# MODULE.net
KiCad netlist of a schematic drawn in Altium Designer
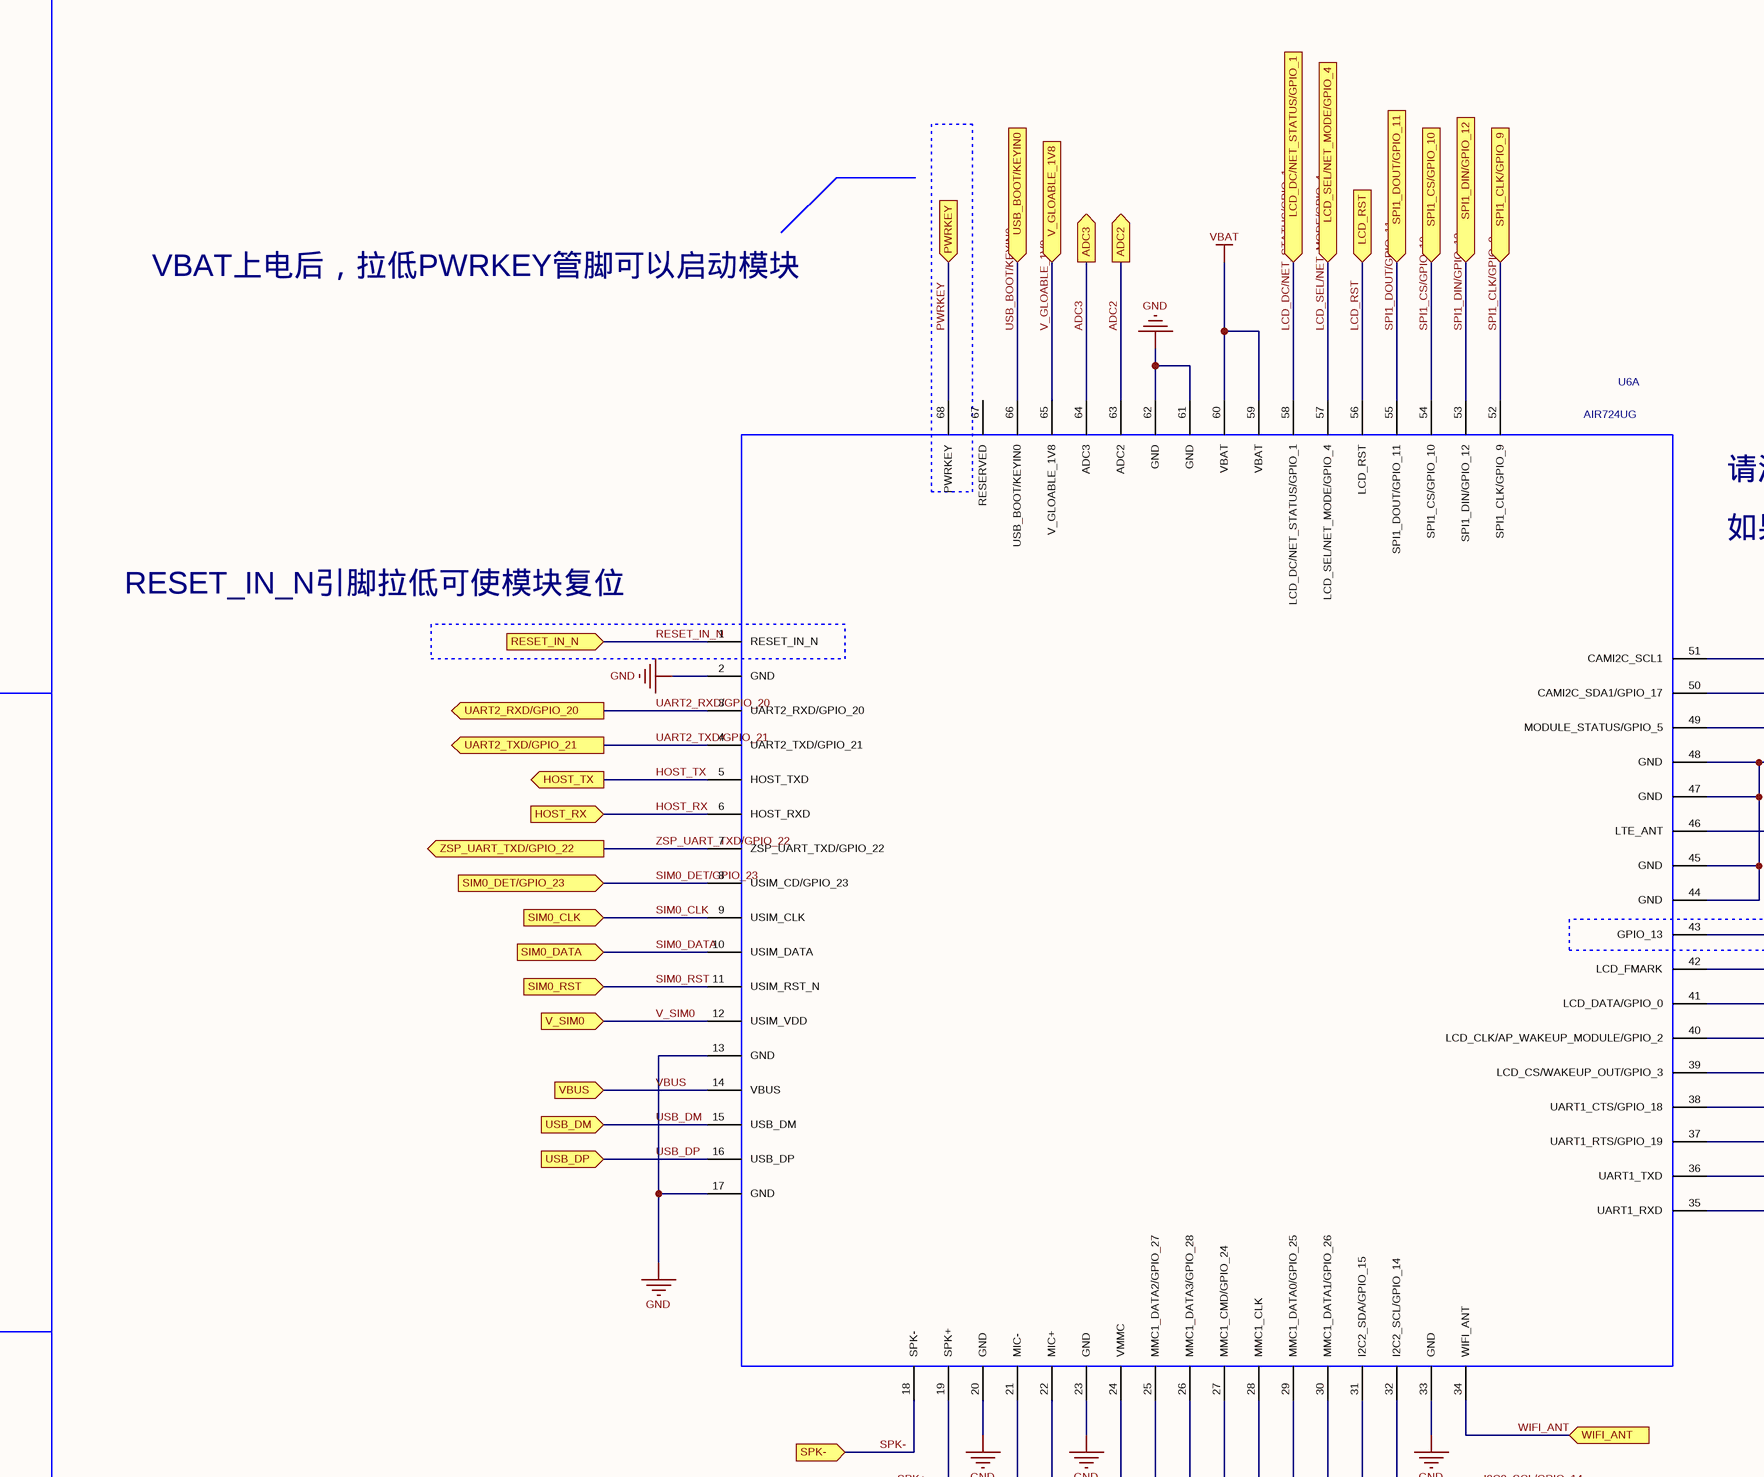
[diagram p0: MODULE.SchDoc, top left]
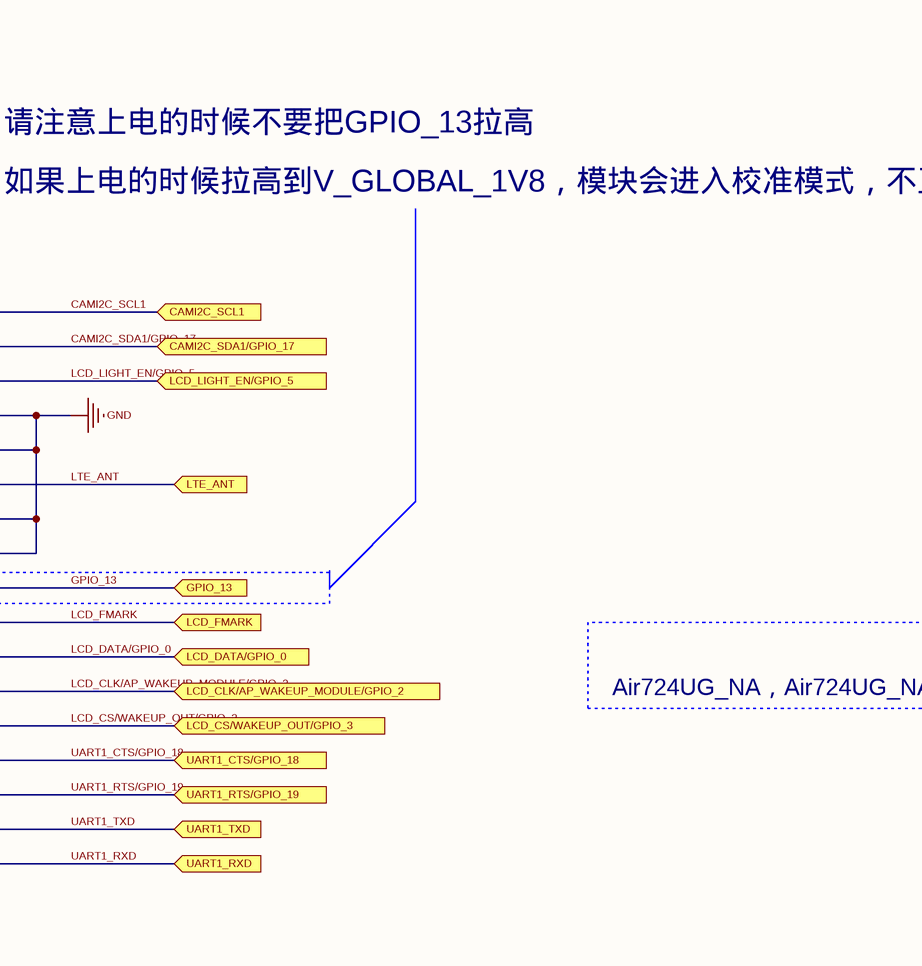
[diagram p1: MODULE.SchDoc, top middle]
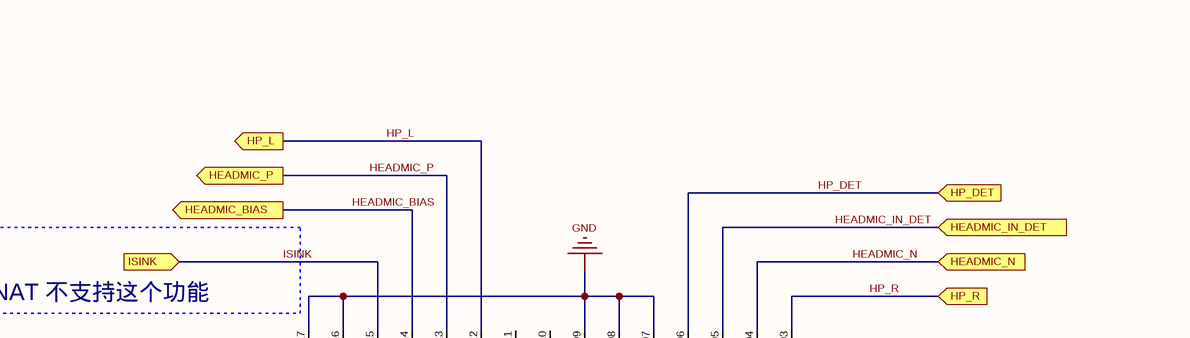
[diagram p2: MODULE.SchDoc, top right]
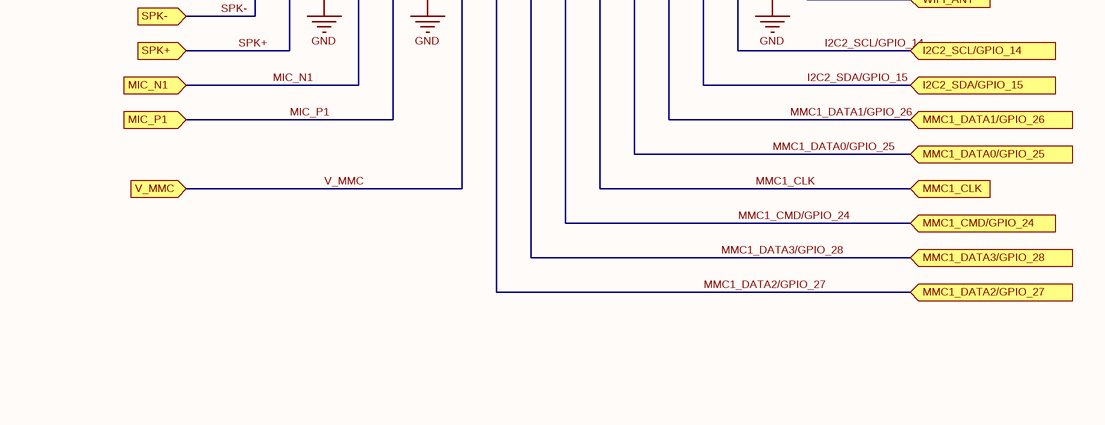
[diagram p3: MODULE.SchDoc, bottom left]
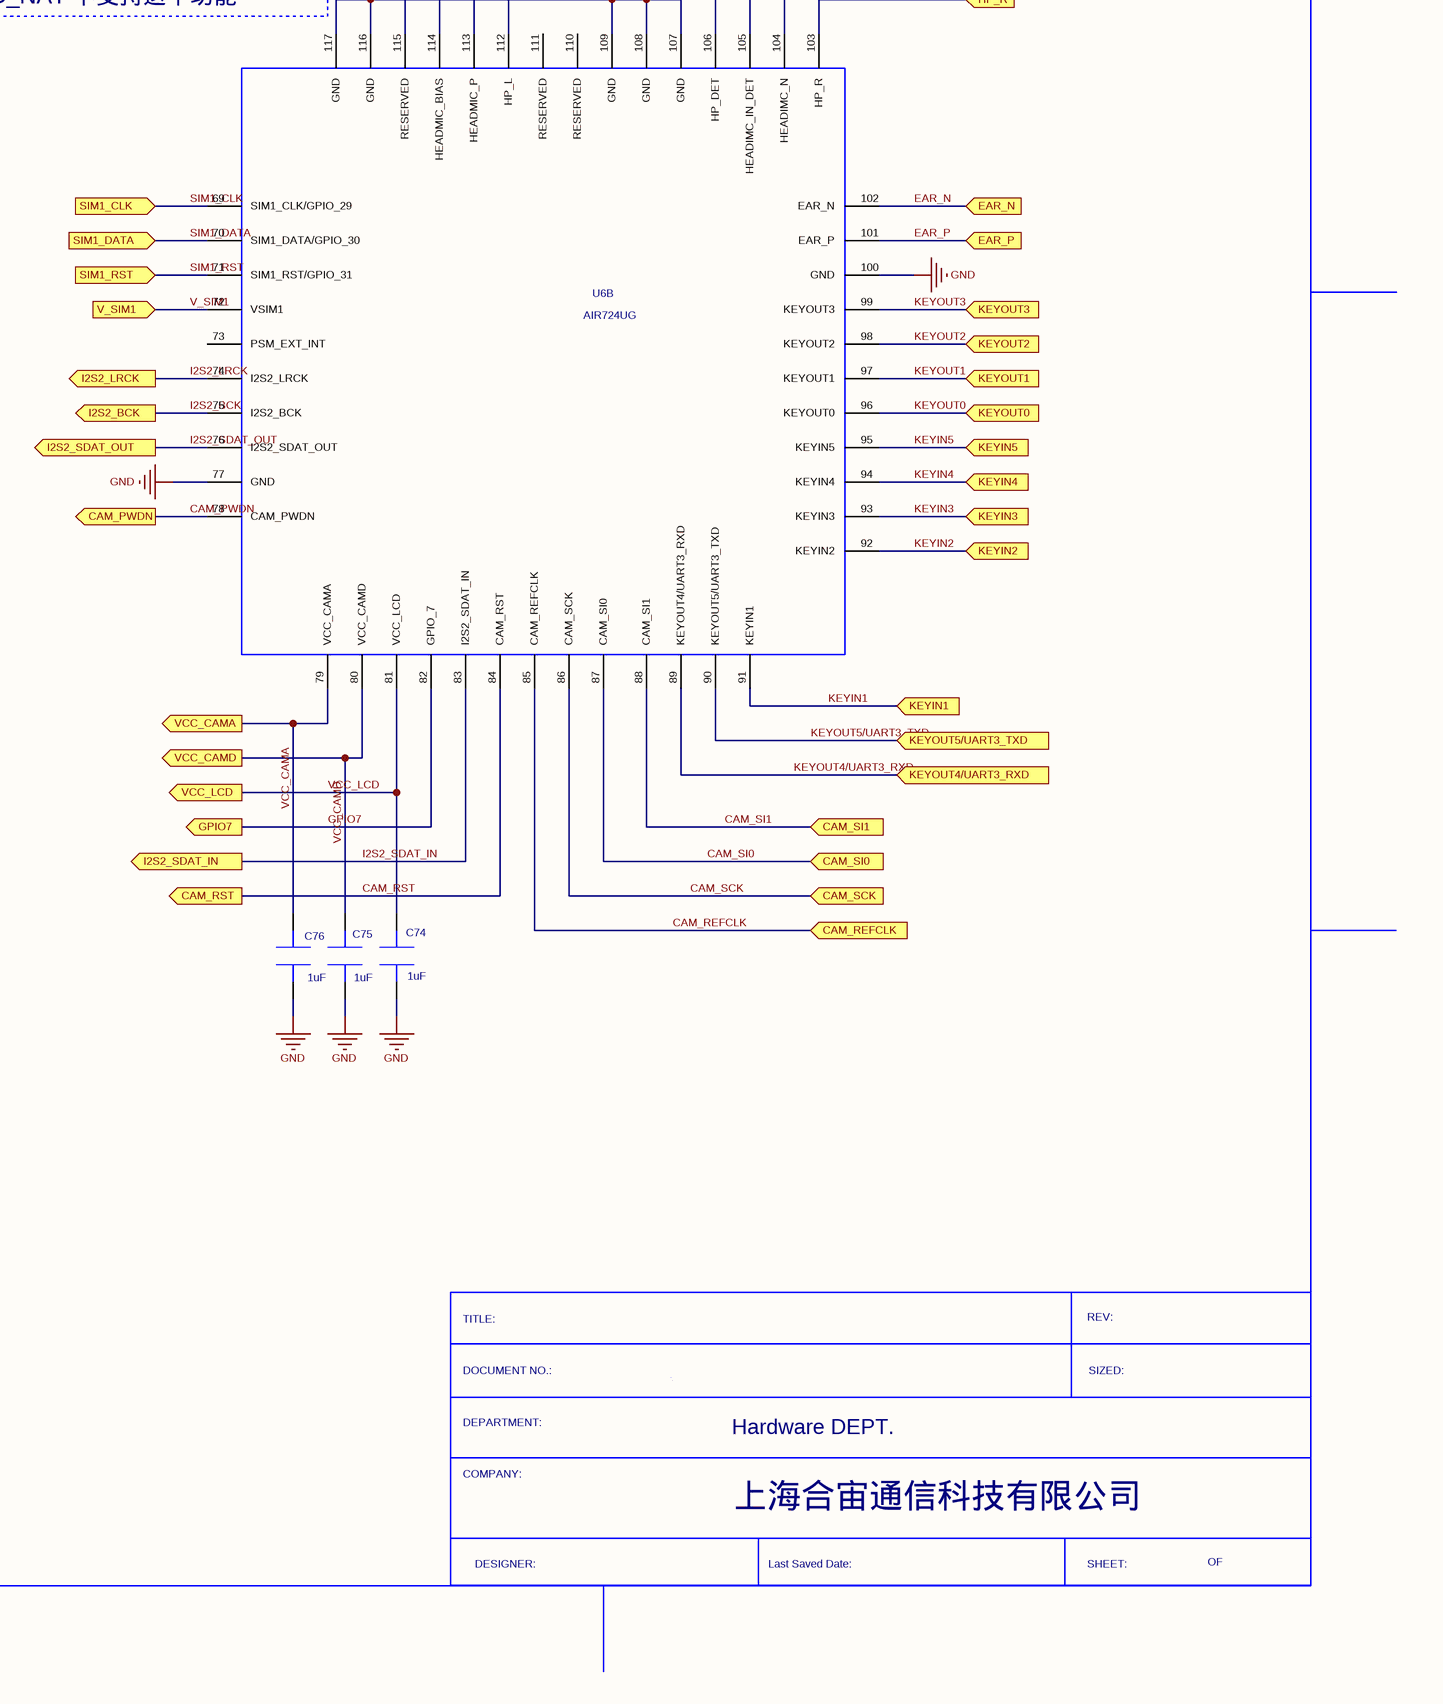
[diagram p4: MODULE.SchDoc, bottom right]

(export (version "E")
  (design (tool "Eeschema 10.0.6"))
  (components
    (comp (ref "C74")
      (value "1uF")
      (footprint "SC0402")
      (description "CAP CER X5R;1uF;+/-10%;6.3V;0402;0.5mm;ROHS")
      (fields (field (name "TOLERANCE") "+/-10%") (field (name "Comment") "CAP-1UF-0402-X5R"))
      (libsource (lib "*") (part "CAP-1UF-0402-X5R"))
    )
    (comp (ref "C75")
      (value "1uF")
      (footprint "SC0402")
      (description "CAP CER X5R;1uF;+/-10%;6.3V;0402;0.5mm;ROHS")
      (fields (field (name "TOLERANCE") "+/-10%") (field (name "Comment") "CAP-1UF-0402-X5R"))
      (libsource (lib "*") (part "CAP-1UF-0402-X5R"))
    )
    (comp (ref "C76")
      (value "1uF")
      (footprint "SC0402")
      (description "CAP CER X5R;1uF;+/-10%;6.3V;0402;0.5mm;ROHS")
      (fields (field (name "TOLERANCE") "+/-10%") (field (name "Comment") "CAP-1UF-0402-X5R"))
      (libsource (lib "*") (part "CAP-1UF-0402-X5R"))
    )
    (comp (ref "U6")
      (value "AIR724UG")
      (footprint "AIR724UG")
      (description "Air724UG")
      (libsource (lib "*") (part "AIR724UG"))
    )
  )
  (nets
    (net (code "1") (name "/ADC2") (class "Default")
      (node (ref "U6") (pin "63") (pinfunction "ADC2_63") (pintype "passive"))
    )
    (net (code "2") (name "/ADC3") (class "Default")
      (node (ref "U6") (pin "64") (pinfunction "ADC3_64") (pintype "passive"))
    )
    (net (code "3") (name "/CAMI2C_SCL1") (class "Default")
      (node (ref "U6") (pin "51") (pinfunction "CAMI2C_SCL1_51") (pintype "passive"))
    )
    (net (code "4") (name "/CAMI2C_SDA1{slash}GPIO_17") (class "Default")
      (node (ref "U6") (pin "50") (pinfunction "CAMI2C_SDA1/GPIO_17_50") (pintype "passive"))
    )
    (net (code "5") (name "/CAM_PWDN") (class "Default")
      (node (ref "U6") (pin "78") (pinfunction "CAM_PWDN_78") (pintype "passive"))
    )
    (net (code "6") (name "/CAM_REFCLK") (class "Default")
      (node (ref "U6") (pin "85") (pinfunction "CAM_REFCLK_85") (pintype "passive"))
    )
    (net (code "7") (name "/CAM_RST") (class "Default")
      (node (ref "U6") (pin "84") (pinfunction "CAM_RST_84") (pintype "passive"))
    )
    (net (code "8") (name "/CAM_SCK") (class "Default")
      (node (ref "U6") (pin "86") (pinfunction "CAM_SCK_86") (pintype "passive"))
    )
    (net (code "9") (name "/CAM_SI0") (class "Default")
      (node (ref "U6") (pin "87") (pinfunction "CAM_SI0_87") (pintype "passive"))
    )
    (net (code "10") (name "/CAM_SI1") (class "Default")
      (node (ref "U6") (pin "88") (pinfunction "CAM_SI1_88") (pintype "passive"))
    )
    (net (code "11") (name "/EAR_N") (class "Default")
      (node (ref "U6") (pin "102") (pinfunction "EAR_N_102") (pintype "passive"))
    )
    (net (code "12") (name "/EAR_P") (class "Default")
      (node (ref "U6") (pin "101") (pinfunction "EAR_P_101") (pintype "passive"))
    )
    (net (code "13") (name "/GPIO7") (class "Default")
      (node (ref "U6") (pin "82") (pinfunction "GPIO_7_82") (pintype "passive"))
    )
    (net (code "14") (name "/GPIO_13") (class "Default")
      (node (ref "U6") (pin "43") (pinfunction "GPIO_13_43") (pintype "passive"))
    )
    (net (code "15") (name "/HEADMIC_BIAS") (class "Default")
      (node (ref "U6") (pin "114") (pinfunction "HEADMIC_BIAS_114") (pintype "passive"))
    )
    (net (code "16") (name "/HEADMIC_IN_DET") (class "Default")
      (node (ref "U6") (pin "105") (pinfunction "HEADIMC_IN_DET_105") (pintype "passive"))
    )
    (net (code "17") (name "/HEADMIC_N") (class "Default")
      (node (ref "U6") (pin "104") (pinfunction "HEADIMC_N_104") (pintype "passive"))
    )
    (net (code "18") (name "/HEADMIC_P") (class "Default")
      (node (ref "U6") (pin "113") (pinfunction "HEADMIC_P_113") (pintype "passive"))
    )
    (net (code "19") (name "/HOST_RX") (class "Default")
      (node (ref "U6") (pin "6") (pinfunction "HOST_RXD_6") (pintype "passive"))
    )
    (net (code "20") (name "/HOST_TX") (class "Default")
      (node (ref "U6") (pin "5") (pinfunction "HOST_TXD_5") (pintype "passive"))
    )
    (net (code "21") (name "/HP_DET") (class "Default")
      (node (ref "U6") (pin "106") (pinfunction "HP_DET_106") (pintype "passive"))
    )
    (net (code "22") (name "/HP_L") (class "Default")
      (node (ref "U6") (pin "112") (pinfunction "HP_L_112") (pintype "passive"))
    )
    (net (code "23") (name "/HP_R") (class "Default")
      (node (ref "U6") (pin "103") (pinfunction "HP_R_103") (pintype "passive"))
    )
    (net (code "24") (name "/I2C2_SCL{slash}GPIO_14") (class "Default")
      (node (ref "U6") (pin "32") (pinfunction "I2C2_SCL/GPIO_14_32") (pintype "passive"))
    )
    (net (code "25") (name "/I2C2_SDA{slash}GPIO_15") (class "Default")
      (node (ref "U6") (pin "31") (pinfunction "I2C2_SDA/GPIO_15_31") (pintype "passive"))
    )
    (net (code "26") (name "/I2S2_BCK") (class "Default")
      (node (ref "U6") (pin "75") (pinfunction "I2S2_BCK_75") (pintype "passive"))
    )
    (net (code "27") (name "/I2S2_LRCK") (class "Default")
      (node (ref "U6") (pin "74") (pinfunction "I2S2_LRCK_74") (pintype "passive"))
    )
    (net (code "28") (name "/I2S2_SDAT_IN") (class "Default")
      (node (ref "U6") (pin "83") (pinfunction "I2S2_SDAT_IN_83") (pintype "passive"))
    )
    (net (code "29") (name "/I2S2_SDAT_OUT") (class "Default")
      (node (ref "U6") (pin "76") (pinfunction "I2S2_SDAT_OUT_76") (pintype "passive"))
    )
    (net (code "30") (name "/ISINK") (class "Default")
      (node (ref "U6") (pin "115") (pinfunction "RESERVED_115") (pintype "passive"))
    )
    (net (code "31") (name "/KEYIN1") (class "Default")
      (node (ref "U6") (pin "91") (pinfunction "KEYIN1_91") (pintype "passive"))
    )
    (net (code "32") (name "/KEYIN2") (class "Default")
      (node (ref "U6") (pin "92") (pinfunction "KEYIN2_92") (pintype "passive"))
    )
    (net (code "33") (name "/KEYIN3") (class "Default")
      (node (ref "U6") (pin "93") (pinfunction "KEYIN3_93") (pintype "passive"))
    )
    (net (code "34") (name "/KEYIN4") (class "Default")
      (node (ref "U6") (pin "94") (pinfunction "KEYIN4_94") (pintype "passive"))
    )
    (net (code "35") (name "/KEYIN5") (class "Default")
      (node (ref "U6") (pin "95") (pinfunction "KEYIN5_95") (pintype "passive"))
    )
    (net (code "36") (name "/KEYOUT0") (class "Default")
      (node (ref "U6") (pin "96") (pinfunction "KEYOUT0_96") (pintype "passive"))
    )
    (net (code "37") (name "/KEYOUT1") (class "Default")
      (node (ref "U6") (pin "97") (pinfunction "KEYOUT1_97") (pintype "passive"))
    )
    (net (code "38") (name "/KEYOUT2") (class "Default")
      (node (ref "U6") (pin "98") (pinfunction "KEYOUT2_98") (pintype "passive"))
    )
    (net (code "39") (name "/KEYOUT3") (class "Default")
      (node (ref "U6") (pin "99") (pinfunction "KEYOUT3_99") (pintype "passive"))
    )
    (net (code "40") (name "/KEYOUT4{slash}UART3_RXD") (class "Default")
      (node (ref "U6") (pin "89") (pinfunction "KEYOUT4/UART3_RXD_89") (pintype "passive"))
    )
    (net (code "41") (name "/KEYOUT5{slash}UART3_TXD") (class "Default")
      (node (ref "U6") (pin "90") (pinfunction "KEYOUT5/UART3_TXD_90") (pintype "passive"))
    )
    (net (code "42") (name "/LCD_CLK{slash}AP_WAKEUP_MODULE{slash}GPIO_2") (class "Default")
      (node (ref "U6") (pin "40") (pinfunction "LCD_CLK/AP_WAKEUP_MODULE/GPIO_2_40") (pintype "passive"))
    )
    (net (code "43") (name "/LCD_CS{slash}WAKEUP_OUT{slash}GPIO_3") (class "Default")
      (node (ref "U6") (pin "39") (pinfunction "LCD_CS/WAKEUP_OUT/GPIO_3_39") (pintype "passive"))
    )
    (net (code "44") (name "/LCD_DATA{slash}GPIO_0") (class "Default")
      (node (ref "U6") (pin "41") (pinfunction "LCD_DATA/GPIO_0_41") (pintype "passive"))
    )
    (net (code "45") (name "/LCD_DC{slash}NET_STATUS{slash}GPIO_1") (class "Default")
      (node (ref "U6") (pin "58") (pinfunction "LCD_DC/NET_STATUS/GPIO_1_58") (pintype "passive"))
    )
    (net (code "46") (name "/LCD_FMARK") (class "Default")
      (node (ref "U6") (pin "42") (pinfunction "LCD_FMARK_42") (pintype "passive"))
    )
    (net (code "47") (name "/LCD_LIGHT_EN{slash}GPIO_5") (class "Default")
      (node (ref "U6") (pin "49") (pinfunction "MODULE_STATUS/GPIO_5_49") (pintype "passive"))
    )
    (net (code "48") (name "/LCD_RST") (class "Default")
      (node (ref "U6") (pin "56") (pinfunction "LCD_RST_56") (pintype "passive"))
    )
    (net (code "49") (name "/LCD_SEL{slash}NET_MODE{slash}GPIO_4") (class "Default")
      (node (ref "U6") (pin "57") (pinfunction "LCD_SEL/NET_MODE/GPIO_4_57") (pintype "passive"))
    )
    (net (code "50") (name "/LTE_ANT") (class "Default")
      (node (ref "U6") (pin "46") (pinfunction "LTE_ANT_46") (pintype "passive"))
    )
    (net (code "51") (name "/MIC_N1") (class "Default")
      (node (ref "U6") (pin "21") (pinfunction "MIC-_21") (pintype "passive"))
    )
    (net (code "52") (name "/MIC_P1") (class "Default")
      (node (ref "U6") (pin "22") (pinfunction "MIC+_22") (pintype "passive"))
    )
    (net (code "53") (name "/MMC1_CLK") (class "Default")
      (node (ref "U6") (pin "28") (pinfunction "MMC1_CLK_28") (pintype "passive"))
    )
    (net (code "54") (name "/MMC1_CMD{slash}GPIO_24") (class "Default")
      (node (ref "U6") (pin "27") (pinfunction "MMC1_CMD/GPIO_24_27") (pintype "passive"))
    )
    (net (code "55") (name "/MMC1_DATA0{slash}GPIO_25") (class "Default")
      (node (ref "U6") (pin "29") (pinfunction "MMC1_DATA0/GPIO_25_29") (pintype "passive"))
    )
    (net (code "56") (name "/MMC1_DATA1{slash}GPIO_26") (class "Default")
      (node (ref "U6") (pin "30") (pinfunction "MMC1_DATA1/GPIO_26_30") (pintype "passive"))
    )
    (net (code "57") (name "/MMC1_DATA2{slash}GPIO_27") (class "Default")
      (node (ref "U6") (pin "25") (pinfunction "MMC1_DATA2/GPIO_27_25") (pintype "passive"))
    )
    (net (code "58") (name "/MMC1_DATA3{slash}GPIO_28") (class "Default")
      (node (ref "U6") (pin "26") (pinfunction "MMC1_DATA3/GPIO_28_26") (pintype "passive"))
    )
    (net (code "59") (name "/PWRKEY") (class "Default")
      (node (ref "U6") (pin "68") (pinfunction "PWRKEY_68") (pintype "passive"))
    )
    (net (code "60") (name "/RESET_IN_N") (class "Default")
      (node (ref "U6") (pin "1") (pinfunction "RESET_IN_N_1") (pintype "passive"))
    )
    (net (code "61") (name "/SIM0_CLK") (class "Default")
      (node (ref "U6") (pin "9") (pinfunction "USIM_CLK_9") (pintype "passive"))
    )
    (net (code "62") (name "/SIM0_DATA") (class "Default")
      (node (ref "U6") (pin "10") (pinfunction "USIM_DATA_10") (pintype "passive"))
    )
    (net (code "63") (name "/SIM0_DET{slash}GPIO_23") (class "Default")
      (node (ref "U6") (pin "8") (pinfunction "USIM_CD/GPIO_23_8") (pintype "passive"))
    )
    (net (code "64") (name "/SIM0_RST") (class "Default")
      (node (ref "U6") (pin "11") (pinfunction "USIM_RST_N_11") (pintype "passive"))
    )
    (net (code "65") (name "/SIM1_CLK") (class "Default")
      (node (ref "U6") (pin "69") (pinfunction "SIM1_CLK/GPIO_29_69") (pintype "passive"))
    )
    (net (code "66") (name "/SIM1_DATA") (class "Default")
      (node (ref "U6") (pin "70") (pinfunction "SIM1_DATA/GPIO_30_70") (pintype "passive"))
    )
    (net (code "67") (name "/SIM1_RST") (class "Default")
      (node (ref "U6") (pin "71") (pinfunction "SIM1_RST/GPIO_31_71") (pintype "passive"))
    )
    (net (code "68") (name "/SPI1_CLK{slash}GPIO_9") (class "Default")
      (node (ref "U6") (pin "52") (pinfunction "SPI1_CLK/GPIO_9_52") (pintype "passive"))
    )
    (net (code "69") (name "/SPI1_CS{slash}GPIO_10") (class "Default")
      (node (ref "U6") (pin "54") (pinfunction "SPI1_CS/GPIO_10_54") (pintype "passive"))
    )
    (net (code "70") (name "/SPI1_DIN{slash}GPIO_12") (class "Default")
      (node (ref "U6") (pin "53") (pinfunction "SPI1_DIN/GPIO_12_53") (pintype "passive"))
    )
    (net (code "71") (name "/SPI1_DOUT{slash}GPIO_11") (class "Default")
      (node (ref "U6") (pin "55") (pinfunction "SPI1_DOUT/GPIO_11_55") (pintype "passive"))
    )
    (net (code "72") (name "/SPK+") (class "Default")
      (node (ref "U6") (pin "19") (pinfunction "SPK+_19") (pintype "passive"))
    )
    (net (code "73") (name "/SPK-") (class "Default")
      (node (ref "U6") (pin "18") (pinfunction "SPK-_18") (pintype "passive"))
    )
    (net (code "74") (name "/UART1_CTS{slash}GPIO_18") (class "Default")
      (node (ref "U6") (pin "38") (pinfunction "UART1_CTS/GPIO_18_38") (pintype "passive"))
    )
    (net (code "75") (name "/UART1_RTS{slash}GPIO_19") (class "Default")
      (node (ref "U6") (pin "37") (pinfunction "UART1_RTS/GPIO_19_37") (pintype "passive"))
    )
    (net (code "76") (name "/UART1_RXD") (class "Default")
      (node (ref "U6") (pin "35") (pinfunction "UART1_RXD_35") (pintype "passive"))
    )
    (net (code "77") (name "/UART1_TXD") (class "Default")
      (node (ref "U6") (pin "36") (pinfunction "UART1_TXD_36") (pintype "passive"))
    )
    (net (code "78") (name "/UART2_RXD{slash}GPIO_20") (class "Default")
      (node (ref "U6") (pin "3") (pinfunction "UART2_RXD/GPIO_20_3") (pintype "passive"))
    )
    (net (code "79") (name "/UART2_TXD{slash}GPIO_21") (class "Default")
      (node (ref "U6") (pin "4") (pinfunction "UART2_TXD/GPIO_21_4") (pintype "passive"))
    )
    (net (code "80") (name "/USB_BOOT{slash}KEYIN0") (class "Default")
      (node (ref "U6") (pin "66") (pinfunction "USB_BOOT/KEYIN0_66") (pintype "passive"))
    )
    (net (code "81") (name "/USB_DM") (class "Default")
      (node (ref "U6") (pin "15") (pinfunction "USB_DM_15") (pintype "passive"))
    )
    (net (code "82") (name "/USB_DP") (class "Default")
      (node (ref "U6") (pin "16") (pinfunction "USB_DP_16") (pintype "passive"))
    )
    (net (code "83") (name "/VBUS") (class "Default")
      (node (ref "U6") (pin "14") (pinfunction "VBUS_14") (pintype "passive"))
    )
    (net (code "84") (name "/VCC_CAMA") (class "Default")
      (node (ref "C76") (pin "2") (pinfunction "2_2") (pintype "passive"))
      (node (ref "U6") (pin "79") (pinfunction "VCC_CAMA_79") (pintype "passive"))
    )
    (net (code "85") (name "/VCC_CAMD") (class "Default")
      (node (ref "C75") (pin "2") (pinfunction "2_2") (pintype "passive"))
      (node (ref "U6") (pin "80") (pinfunction "VCC_CAMD_80") (pintype "passive"))
    )
    (net (code "86") (name "/VCC_LCD") (class "Default")
      (node (ref "C74") (pin "2") (pinfunction "2_2") (pintype "passive"))
      (node (ref "U6") (pin "81") (pinfunction "VCC_LCD_81") (pintype "passive"))
    )
    (net (code "87") (name "/V_GLOABLE_1V8") (class "Default")
      (node (ref "U6") (pin "65") (pinfunction "V_GLOABLE_1V8_65") (pintype "passive"))
    )
    (net (code "88") (name "/V_MMC") (class "Default")
      (node (ref "U6") (pin "24") (pinfunction "VMMC_24") (pintype "passive"))
    )
    (net (code "89") (name "/V_SIM0") (class "Default")
      (node (ref "U6") (pin "12") (pinfunction "USIM_VDD_12") (pintype "passive"))
    )
    (net (code "90") (name "/V_SIM1") (class "Default")
      (node (ref "U6") (pin "72") (pinfunction "VSIM1_72") (pintype "passive"))
    )
    (net (code "91") (name "/WIFI_ANT") (class "Default")
      (node (ref "U6") (pin "34") (pinfunction "WIFI_ANT_34") (pintype "passive"))
    )
    (net (code "92") (name "/ZSP_UART_TXD{slash}GPIO_22") (class "Default")
      (node (ref "U6") (pin "7") (pinfunction "ZSP_UART_TXD/GPIO_22_7") (pintype "passive"))
    )
    (net (code "93") (name "GND") (class "Default")
      (node (ref "C74") (pin "1") (pinfunction "1_1") (pintype "passive"))
      (node (ref "C75") (pin "1") (pinfunction "1_1") (pintype "passive"))
      (node (ref "C76") (pin "1") (pinfunction "1_1") (pintype "passive"))
      (node (ref "U6") (pin "100") (pinfunction "GND_100") (pintype "passive"))
      (node (ref "U6") (pin "107") (pinfunction "GND_107") (pintype "passive"))
      (node (ref "U6") (pin "108") (pinfunction "GND_108") (pintype "passive"))
      (node (ref "U6") (pin "109") (pinfunction "GND_109") (pintype "passive"))
      (node (ref "U6") (pin "116") (pinfunction "GND_116") (pintype "passive"))
      (node (ref "U6") (pin "117") (pinfunction "GND_117") (pintype "passive"))
      (node (ref "U6") (pin "13") (pinfunction "GND_13") (pintype "passive"))
      (node (ref "U6") (pin "17") (pinfunction "GND_17") (pintype "passive"))
      (node (ref "U6") (pin "2") (pinfunction "GND_2") (pintype "passive"))
      (node (ref "U6") (pin "20") (pinfunction "GND_20") (pintype "passive"))
      (node (ref "U6") (pin "23") (pinfunction "GND_23") (pintype "passive"))
      (node (ref "U6") (pin "33") (pinfunction "GND_33") (pintype "passive"))
      (node (ref "U6") (pin "44") (pinfunction "GND_44") (pintype "passive"))
      (node (ref "U6") (pin "45") (pinfunction "GND_45") (pintype "passive"))
      (node (ref "U6") (pin "47") (pinfunction "GND_47") (pintype "passive"))
      (node (ref "U6") (pin "48") (pinfunction "GND_48") (pintype "passive"))
      (node (ref "U6") (pin "61") (pinfunction "GND_61") (pintype "passive"))
      (node (ref "U6") (pin "62") (pinfunction "GND_62") (pintype "passive"))
      (node (ref "U6") (pin "77") (pinfunction "GND_77") (pintype "passive"))
    )
    (net (code "94") (name "VBAT") (class "Default")
      (node (ref "U6") (pin "59") (pinfunction "VBAT_59") (pintype "passive"))
      (node (ref "U6") (pin "60") (pinfunction "VBAT_60") (pintype "passive"))
    )
    (net (code "95") (name "unconnected-(U6A-RESERVED-Pad67)") (class "Default")
      (node (ref "U6") (pin "67") (pinfunction "RESERVED_67") (pintype "passive"))
    )
    (net (code "96") (name "unconnected-(U6B-PSM_EXT_INT-Pad73)") (class "Default")
      (node (ref "U6") (pin "73") (pinfunction "PSM_EXT_INT_73") (pintype "passive"))
    )
    (net (code "97") (name "unconnected-(U6B-RESERVED-Pad110)") (class "Default")
      (node (ref "U6") (pin "110") (pinfunction "RESERVED_110") (pintype "passive"))
    )
    (net (code "98") (name "unconnected-(U6B-RESERVED-Pad111)") (class "Default")
      (node (ref "U6") (pin "111") (pinfunction "RESERVED_111") (pintype "passive"))
    )
  )
)
